# board1.net
KiCad netlist of a schematic drawn in Altium Designer
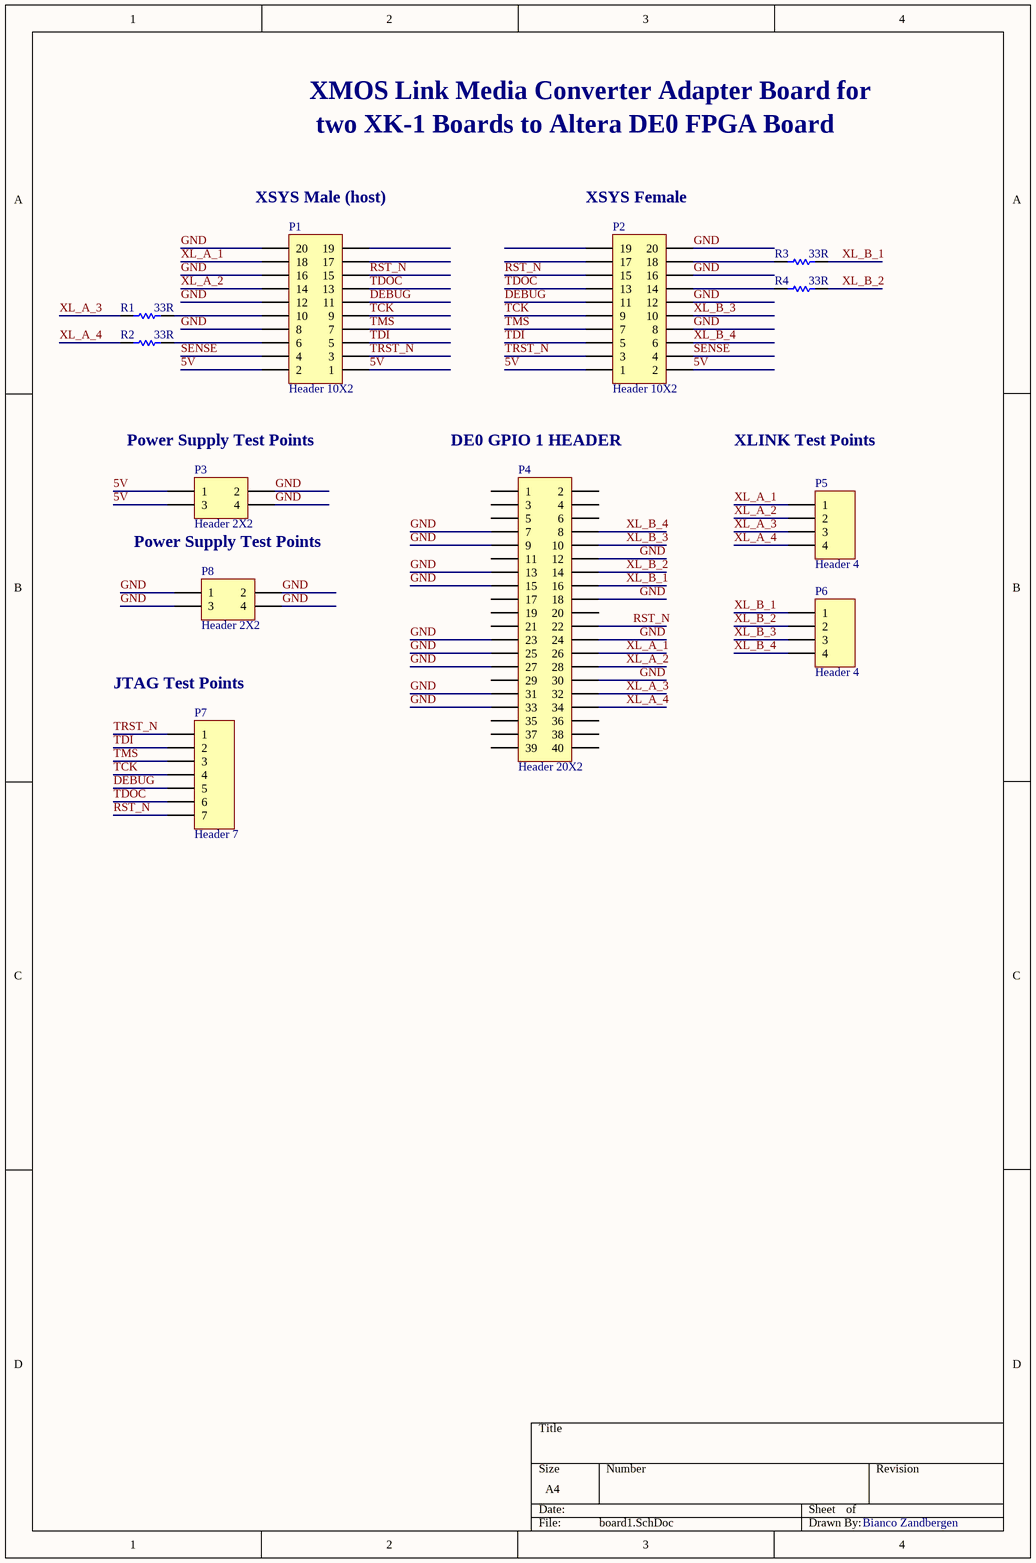
[diagram p0: board1.SchDoc]

(export (version "E")
  (design (tool "Eeschema 10.0.6"))
  (components
    (comp (ref "P1")
      (value "Header 10X2")
      (footprint "HDR2X10")
      (description "Header, 10-Pin, Dual row")
      (fields (field (name "PUBLISHER") "Altium Limited"))
      (libsource (lib "") (part "Header 10X2_1"))
    )
    (comp (ref "P2")
      (value "Header 10X2")
      (footprint "HDR2X10_MIRROR")
      (description "Header, 10-Pin, Dual row")
      (fields (field (name "PUBLISHER") "Altium Limited"))
      (libsource (lib "Miscellaneous Connectors") (part "Header 10X2"))
    )
    (comp (ref "P3")
      (value "Header 2X2")
      (footprint "HDR2X2")
      (description "Header, 2-Pin, Dual row")
      (fields (field (name "PUBLISHER") "Altium Limited"))
      (libsource (lib "Miscellaneous Connectors") (part "Header 2X2"))
    )
    (comp (ref "P4")
      (value "Header 20X2")
      (footprint "HDR2X20")
      (description "Header, 20-Pin, Dual row")
      (fields (field (name "PUBLISHER") "Altium Limited"))
      (libsource (lib "Miscellaneous Connectors") (part "Header 20X2"))
    )
    (comp (ref "P5")
      (value "Header 4")
      (footprint "HDR1X4")
      (description "Header, 4-Pin")
      (fields (field (name "PUBLISHER") "Altium Limited"))
      (libsource (lib "Miscellaneous Connectors") (part "Header 4"))
    )
    (comp (ref "P6")
      (value "Header 4")
      (footprint "HDR1X4")
      (description "Header, 4-Pin")
      (fields (field (name "PUBLISHER") "Altium Limited"))
      (libsource (lib "Miscellaneous Connectors") (part "Header 4"))
    )
    (comp (ref "P7")
      (value "Header 7")
      (footprint "HDR1X7")
      (description "Header, 7-Pin")
      (fields (field (name "PUBLISHER") "Altium Limited"))
      (libsource (lib "Miscellaneous Connectors") (part "Header 7"))
    )
    (comp (ref "P8")
      (value "Header 2X2")
      (footprint "HDR2X2")
      (description "Header, 2-Pin, Dual row")
      (fields (field (name "PUBLISHER") "Altium Limited"))
      (libsource (lib "Miscellaneous Connectors") (part "Header 2X2"))
    )
    (comp (ref "R1")
      (value "33R")
      (footprint "2012[0805]_RES")
      (description "Resistor")
      (fields (field (name "Comment") "Res1") (field (name "PUBLISHER") "Altium Limited"))
      (libsource (lib "audio_delay") (part "Res1"))
    )
    (comp (ref "R2")
      (value "33R")
      (footprint "2012[0805]_RES")
      (description "Resistor")
      (fields (field (name "Comment") "Res1") (field (name "PUBLISHER") "Altium Limited"))
      (libsource (lib "audio_delay") (part "Res1"))
    )
    (comp (ref "R3")
      (value "33R")
      (footprint "2012[0805]_RES")
      (description "Resistor")
      (fields (field (name "Comment") "Res1") (field (name "PUBLISHER") "Altium Limited"))
      (libsource (lib "audio_delay") (part "Res1"))
    )
    (comp (ref "R4")
      (value "33R")
      (footprint "2012[0805]_RES")
      (description "Resistor")
      (fields (field (name "Comment") "Res1") (field (name "PUBLISHER") "Altium Limited"))
      (libsource (lib "audio_delay") (part "Res1"))
    )
  )
  (nets
    (net (code "1") (name "/5V") (class "Default")
      (node (ref "P1") (pin "1") (pinfunction "1_1") (pintype "passive"))
      (node (ref "P1") (pin "2") (pinfunction "2_2") (pintype "passive"))
      (node (ref "P2") (pin "1") (pinfunction "1_1") (pintype "passive"))
      (node (ref "P2") (pin "2") (pinfunction "2_2") (pintype "passive"))
      (node (ref "P3") (pin "1") (pinfunction "1_1") (pintype "passive"))
      (node (ref "P3") (pin "3") (pinfunction "3_3") (pintype "passive"))
    )
    (net (code "2") (name "/DEBUG") (class "Default")
      (node (ref "P1") (pin "11") (pinfunction "11_11") (pintype "passive"))
      (node (ref "P2") (pin "11") (pinfunction "11_11") (pintype "passive"))
      (node (ref "P7") (pin "5") (pinfunction "5_5") (pintype "passive"))
    )
    (net (code "3") (name "/GND") (class "Default")
      (node (ref "P1") (pin "12") (pinfunction "12_12") (pintype "passive"))
      (node (ref "P1") (pin "16") (pinfunction "16_16") (pintype "passive"))
      (node (ref "P1") (pin "20") (pinfunction "20_20") (pintype "passive"))
      (node (ref "P1") (pin "8") (pinfunction "8_8") (pintype "passive"))
      (node (ref "P2") (pin "12") (pinfunction "12_12") (pintype "passive"))
      (node (ref "P2") (pin "16") (pinfunction "16_16") (pintype "passive"))
      (node (ref "P2") (pin "20") (pinfunction "20_20") (pintype "passive"))
      (node (ref "P2") (pin "8") (pinfunction "8_8") (pintype "passive"))
      (node (ref "P3") (pin "2") (pinfunction "2_2") (pintype "passive"))
      (node (ref "P3") (pin "4") (pinfunction "4_4") (pintype "passive"))
      (node (ref "P4") (pin "12") (pinfunction "12_12") (pintype "passive"))
      (node (ref "P4") (pin "13") (pinfunction "13_13") (pintype "passive"))
      (node (ref "P4") (pin "15") (pinfunction "15_15") (pintype "passive"))
      (node (ref "P4") (pin "18") (pinfunction "18_18") (pintype "passive"))
      (node (ref "P4") (pin "23") (pinfunction "23_23") (pintype "passive"))
      (node (ref "P4") (pin "24") (pinfunction "24_24") (pintype "passive"))
      (node (ref "P4") (pin "25") (pinfunction "25_25") (pintype "passive"))
      (node (ref "P4") (pin "27") (pinfunction "27_27") (pintype "passive"))
      (node (ref "P4") (pin "30") (pinfunction "30_30") (pintype "passive"))
      (node (ref "P4") (pin "31") (pinfunction "31_31") (pintype "passive"))
      (node (ref "P4") (pin "33") (pinfunction "33_33") (pintype "passive"))
      (node (ref "P4") (pin "7") (pinfunction "7_7") (pintype "passive"))
      (node (ref "P4") (pin "9") (pinfunction "9_9") (pintype "passive"))
      (node (ref "P8") (pin "1") (pinfunction "1_1") (pintype "passive"))
      (node (ref "P8") (pin "2") (pinfunction "2_2") (pintype "passive"))
      (node (ref "P8") (pin "3") (pinfunction "3_3") (pintype "passive"))
      (node (ref "P8") (pin "4") (pinfunction "4_4") (pintype "passive"))
    )
    (net (code "4") (name "/RST_N") (class "Default")
      (node (ref "P1") (pin "15") (pinfunction "15_15") (pintype "passive"))
      (node (ref "P2") (pin "15") (pinfunction "15_15") (pintype "passive"))
      (node (ref "P4") (pin "22") (pinfunction "22_22") (pintype "passive"))
      (node (ref "P7") (pin "7") (pinfunction "7_7") (pintype "passive"))
    )
    (net (code "5") (name "/SENSE") (class "Default")
      (node (ref "P1") (pin "4") (pinfunction "4_4") (pintype "passive"))
      (node (ref "P2") (pin "4") (pinfunction "4_4") (pintype "passive"))
    )
    (net (code "6") (name "/TCK") (class "Default")
      (node (ref "P1") (pin "9") (pinfunction "9_9") (pintype "passive"))
      (node (ref "P2") (pin "9") (pinfunction "9_9") (pintype "passive"))
      (node (ref "P7") (pin "4") (pinfunction "4_4") (pintype "passive"))
    )
    (net (code "7") (name "/TDI") (class "Default")
      (node (ref "P1") (pin "5") (pinfunction "5_5") (pintype "passive"))
      (node (ref "P2") (pin "5") (pinfunction "5_5") (pintype "passive"))
      (node (ref "P7") (pin "2") (pinfunction "2_2") (pintype "passive"))
    )
    (net (code "8") (name "/TDOC") (class "Default")
      (node (ref "P1") (pin "13") (pinfunction "13_13") (pintype "passive"))
      (node (ref "P2") (pin "13") (pinfunction "13_13") (pintype "passive"))
      (node (ref "P7") (pin "6") (pinfunction "6_6") (pintype "passive"))
    )
    (net (code "9") (name "/TMS") (class "Default")
      (node (ref "P1") (pin "7") (pinfunction "7_7") (pintype "passive"))
      (node (ref "P2") (pin "7") (pinfunction "7_7") (pintype "passive"))
      (node (ref "P7") (pin "3") (pinfunction "3_3") (pintype "passive"))
    )
    (net (code "10") (name "/TRST_N") (class "Default")
      (node (ref "P1") (pin "3") (pinfunction "3_3") (pintype "passive"))
      (node (ref "P2") (pin "3") (pinfunction "3_3") (pintype "passive"))
      (node (ref "P7") (pin "1") (pinfunction "1_1") (pintype "passive"))
    )
    (net (code "11") (name "/XL_A_1") (class "Default")
      (node (ref "P1") (pin "18") (pinfunction "18_18") (pintype "passive"))
      (node (ref "P4") (pin "26") (pinfunction "26_26") (pintype "passive"))
      (node (ref "P5") (pin "1") (pinfunction "1_1") (pintype "passive"))
    )
    (net (code "12") (name "/XL_A_2") (class "Default")
      (node (ref "P1") (pin "14") (pinfunction "14_14") (pintype "passive"))
      (node (ref "P4") (pin "28") (pinfunction "28_28") (pintype "passive"))
      (node (ref "P5") (pin "2") (pinfunction "2_2") (pintype "passive"))
    )
    (net (code "13") (name "/XL_A_3") (class "Default")
      (node (ref "P4") (pin "32") (pinfunction "32_32") (pintype "passive"))
      (node (ref "P5") (pin "3") (pinfunction "3_3") (pintype "passive"))
      (node (ref "R1") (pin "1") (pinfunction "1_1") (pintype "passive"))
    )
    (net (code "14") (name "/XL_A_4") (class "Default")
      (node (ref "P4") (pin "34") (pinfunction "34_34") (pintype "passive"))
      (node (ref "P5") (pin "4") (pinfunction "4_4") (pintype "passive"))
      (node (ref "R2") (pin "1") (pinfunction "1_1") (pintype "passive"))
    )
    (net (code "15") (name "/XL_B_1") (class "Default")
      (node (ref "P4") (pin "16") (pinfunction "16_16") (pintype "passive"))
      (node (ref "P6") (pin "1") (pinfunction "1_1") (pintype "passive"))
      (node (ref "R3") (pin "2") (pinfunction "2_2") (pintype "passive"))
    )
    (net (code "16") (name "/XL_B_2") (class "Default")
      (node (ref "P4") (pin "14") (pinfunction "14_14") (pintype "passive"))
      (node (ref "P6") (pin "2") (pinfunction "2_2") (pintype "passive"))
      (node (ref "R4") (pin "2") (pinfunction "2_2") (pintype "passive"))
    )
    (net (code "17") (name "/XL_B_3") (class "Default")
      (node (ref "P2") (pin "10") (pinfunction "10_10") (pintype "passive"))
      (node (ref "P4") (pin "10") (pinfunction "10_10") (pintype "passive"))
      (node (ref "P6") (pin "3") (pinfunction "3_3") (pintype "passive"))
    )
    (net (code "18") (name "/XL_B_4") (class "Default")
      (node (ref "P2") (pin "6") (pinfunction "6_6") (pintype "passive"))
      (node (ref "P4") (pin "8") (pinfunction "8_8") (pintype "passive"))
      (node (ref "P6") (pin "4") (pinfunction "4_4") (pintype "passive"))
    )
    (net (code "19") (name "Net-(P1-Pad6)") (class "Default")
      (node (ref "P1") (pin "6") (pinfunction "6_6") (pintype "passive"))
      (node (ref "R2") (pin "2") (pinfunction "2_2") (pintype "passive"))
    )
    (net (code "20") (name "Net-(P1-Pad10)") (class "Default")
      (node (ref "P1") (pin "10") (pinfunction "10_10") (pintype "passive"))
      (node (ref "R1") (pin "2") (pinfunction "2_2") (pintype "passive"))
    )
    (net (code "21") (name "Net-(P2-Pad14)") (class "Default")
      (node (ref "P2") (pin "14") (pinfunction "14_14") (pintype "passive"))
      (node (ref "R4") (pin "1") (pinfunction "1_1") (pintype "passive"))
    )
    (net (code "22") (name "Net-(P2-Pad18)") (class "Default")
      (node (ref "P2") (pin "18") (pinfunction "18_18") (pintype "passive"))
      (node (ref "R3") (pin "1") (pinfunction "1_1") (pintype "passive"))
    )
    (net (code "23") (name "unconnected-(P1-Pad17)") (class "Default")
      (node (ref "P1") (pin "17") (pinfunction "17_17") (pintype "passive"))
    )
    (net (code "24") (name "unconnected-(P1-Pad19)") (class "Default")
      (node (ref "P1") (pin "19") (pinfunction "19_19") (pintype "passive"))
    )
    (net (code "25") (name "unconnected-(P2-Pad17)") (class "Default")
      (node (ref "P2") (pin "17") (pinfunction "17_17") (pintype "passive"))
    )
    (net (code "26") (name "unconnected-(P2-Pad19)") (class "Default")
      (node (ref "P2") (pin "19") (pinfunction "19_19") (pintype "passive"))
    )
    (net (code "27") (name "unconnected-(P4-Pad1)") (class "Default")
      (node (ref "P4") (pin "1") (pinfunction "1_1") (pintype "passive"))
    )
    (net (code "28") (name "unconnected-(P4-Pad2)") (class "Default")
      (node (ref "P4") (pin "2") (pinfunction "2_2") (pintype "passive"))
    )
    (net (code "29") (name "unconnected-(P4-Pad3)") (class "Default")
      (node (ref "P4") (pin "3") (pinfunction "3_3") (pintype "passive"))
    )
    (net (code "30") (name "unconnected-(P4-Pad4)") (class "Default")
      (node (ref "P4") (pin "4") (pinfunction "4_4") (pintype "passive"))
    )
    (net (code "31") (name "unconnected-(P4-Pad5)") (class "Default")
      (node (ref "P4") (pin "5") (pinfunction "5_5") (pintype "passive"))
    )
    (net (code "32") (name "unconnected-(P4-Pad6)") (class "Default")
      (node (ref "P4") (pin "6") (pinfunction "6_6") (pintype "passive"))
    )
    (net (code "33") (name "unconnected-(P4-Pad11)") (class "Default")
      (node (ref "P4") (pin "11") (pinfunction "11_11") (pintype "passive"))
    )
    (net (code "34") (name "unconnected-(P4-Pad17)") (class "Default")
      (node (ref "P4") (pin "17") (pinfunction "17_17") (pintype "passive"))
    )
    (net (code "35") (name "unconnected-(P4-Pad19)") (class "Default")
      (node (ref "P4") (pin "19") (pinfunction "19_19") (pintype "passive"))
    )
    (net (code "36") (name "unconnected-(P4-Pad20)") (class "Default")
      (node (ref "P4") (pin "20") (pinfunction "20_20") (pintype "passive"))
    )
    (net (code "37") (name "unconnected-(P4-Pad21)") (class "Default")
      (node (ref "P4") (pin "21") (pinfunction "21_21") (pintype "passive"))
    )
    (net (code "38") (name "unconnected-(P4-Pad29)") (class "Default")
      (node (ref "P4") (pin "29") (pinfunction "29_29") (pintype "passive"))
    )
    (net (code "39") (name "unconnected-(P4-Pad35)") (class "Default")
      (node (ref "P4") (pin "35") (pinfunction "35_35") (pintype "passive"))
    )
    (net (code "40") (name "unconnected-(P4-Pad36)") (class "Default")
      (node (ref "P4") (pin "36") (pinfunction "36_36") (pintype "passive"))
    )
    (net (code "41") (name "unconnected-(P4-Pad37)") (class "Default")
      (node (ref "P4") (pin "37") (pinfunction "37_37") (pintype "passive"))
    )
    (net (code "42") (name "unconnected-(P4-Pad38)") (class "Default")
      (node (ref "P4") (pin "38") (pinfunction "38_38") (pintype "passive"))
    )
    (net (code "43") (name "unconnected-(P4-Pad39)") (class "Default")
      (node (ref "P4") (pin "39") (pinfunction "39_39") (pintype "passive"))
    )
    (net (code "44") (name "unconnected-(P4-Pad40)") (class "Default")
      (node (ref "P4") (pin "40") (pinfunction "40_40") (pintype "passive"))
    )
  )
)
